# SCH_Boat_automator_2_0_2022-10-05.net
KiCad netlist of a schematic drawn in EasyEDA
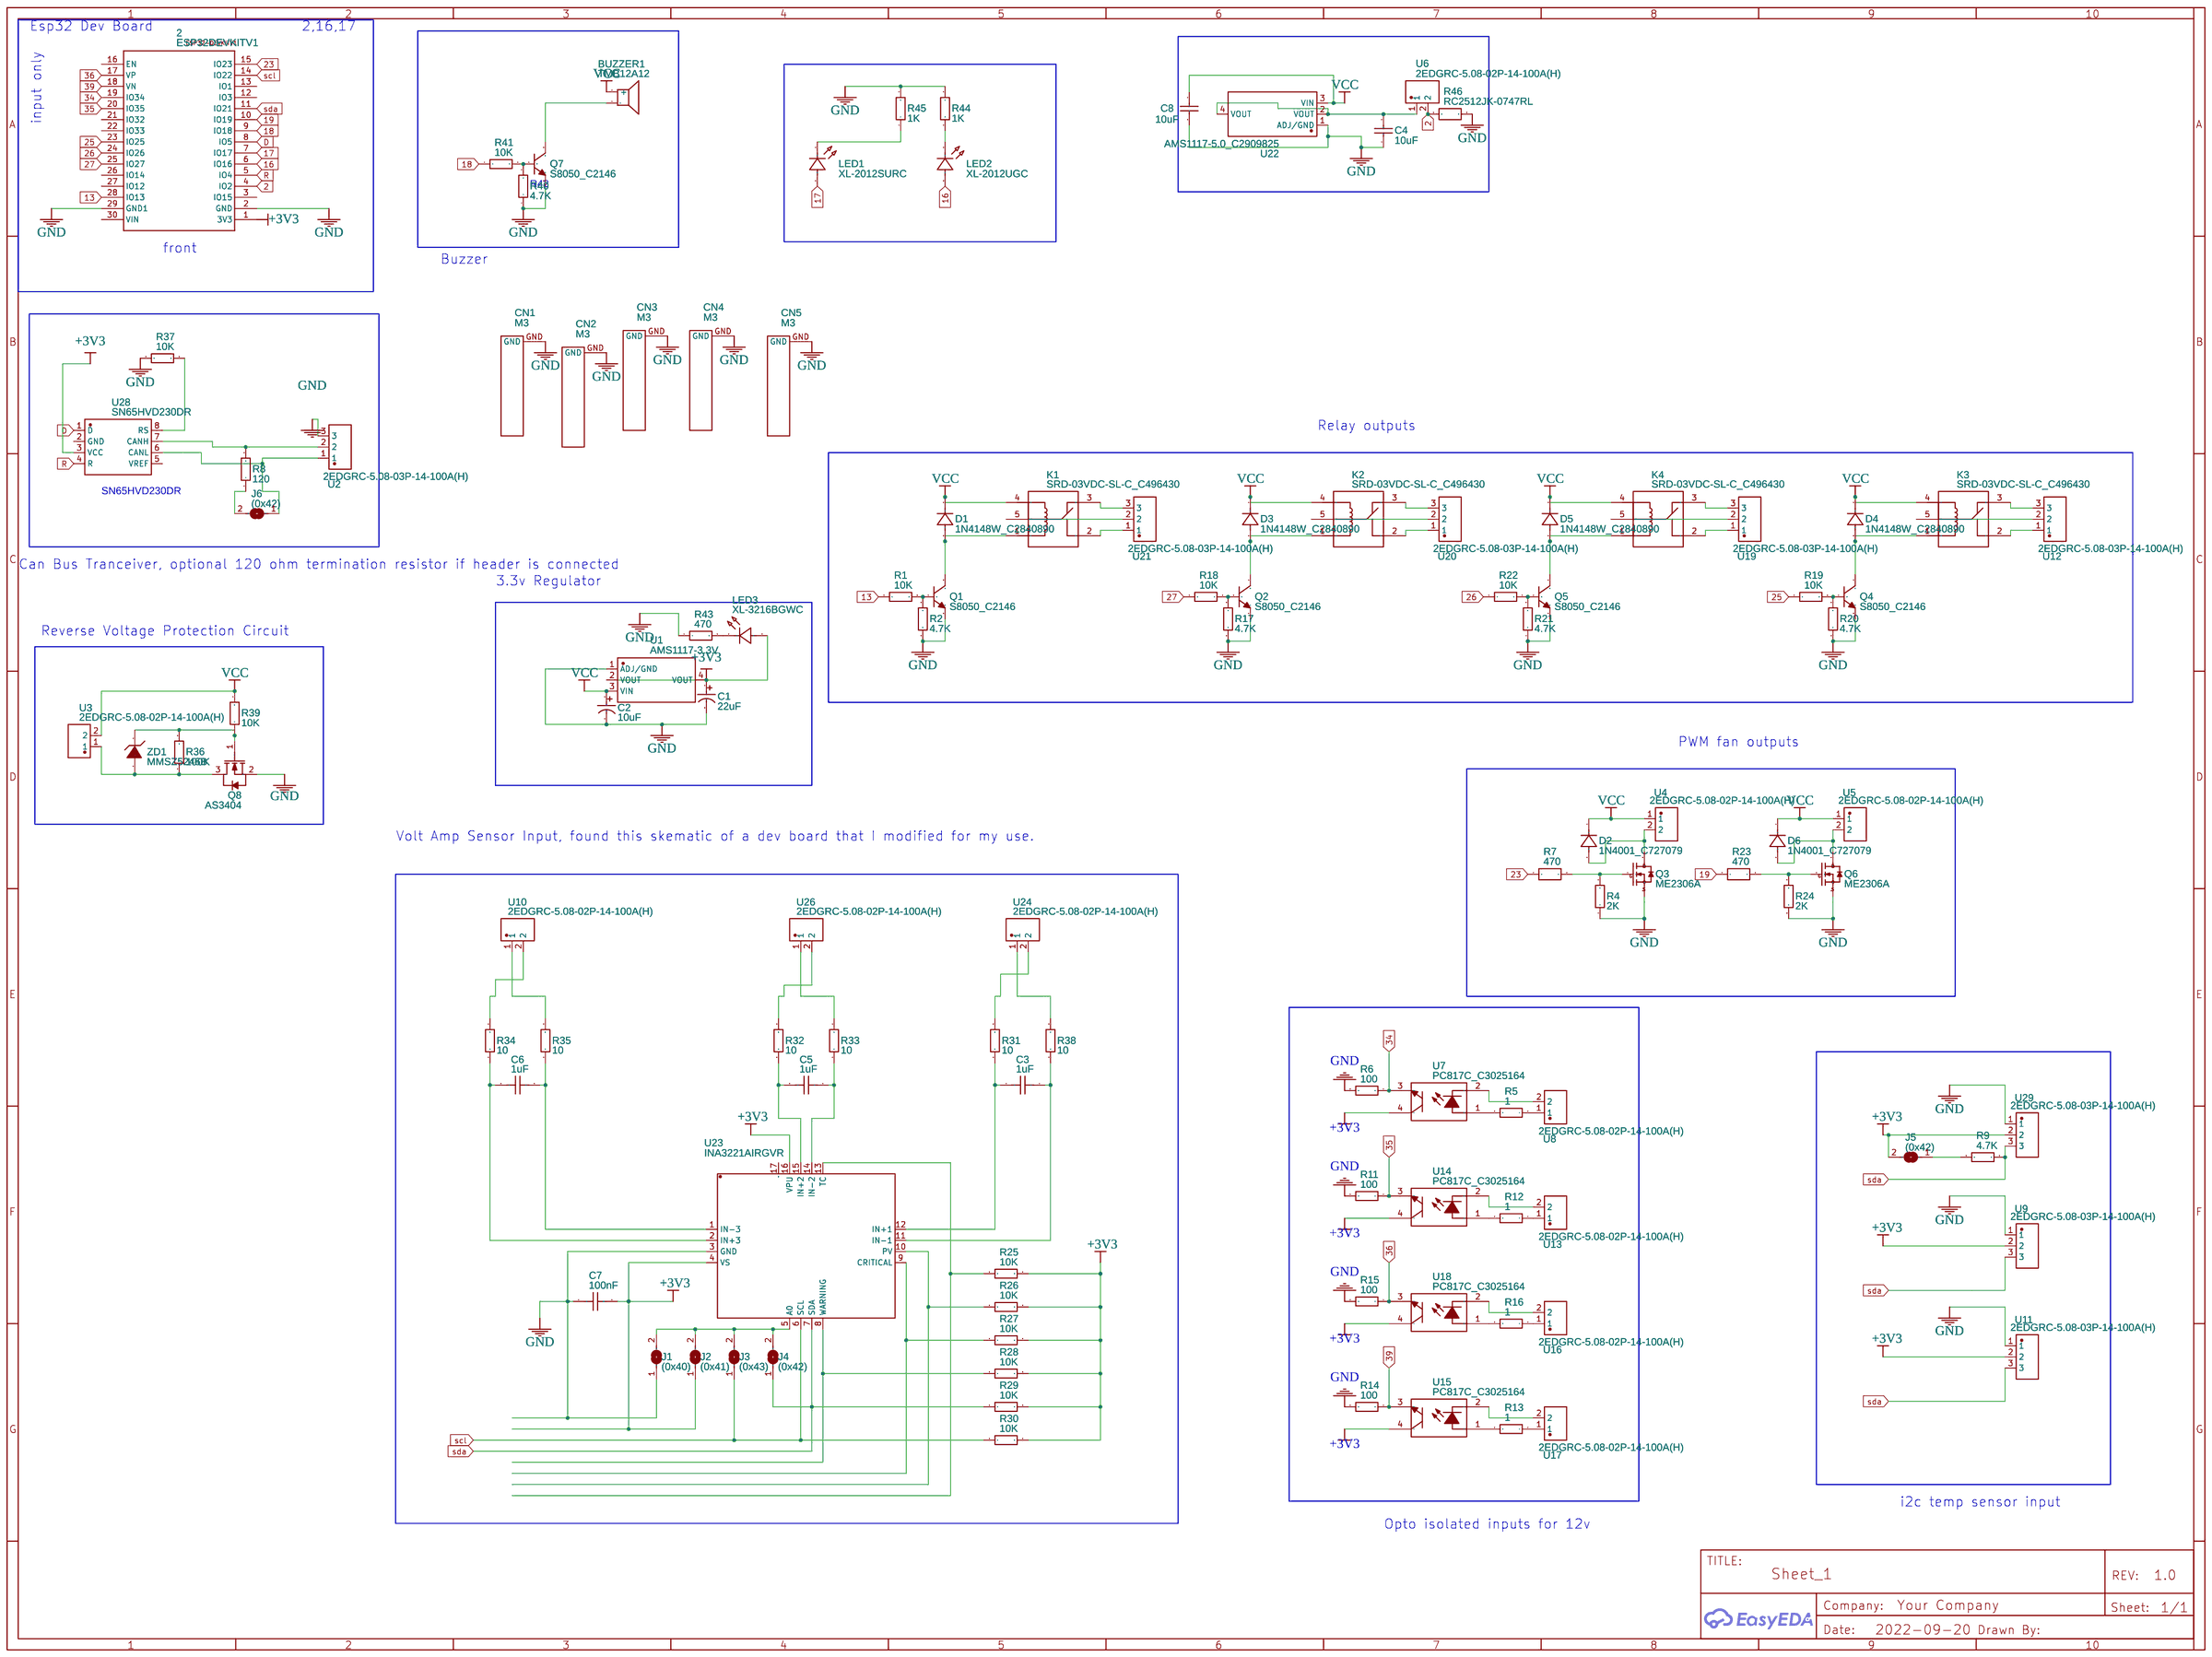
[diagram p0: schematic sheet]

(export (version "E")
  (design (tool "Eeschema 10.0.6"))
  (components
    (comp (ref "2") (value "ESP32DEVKITV1") (libsource (lib "") (part "ESP32DEVKITV1")))
    (comp (ref "BUZZER1")
      (value "TMB12A12")
      (fields (field (name "BOM_Supplier Part") "C96079"))
      (libsource (lib "") (part "TMB12A12"))
    )
    (comp (ref "C1")
      (value "22uF")
      (fields
        (field (name "BOM_Manufacturer Part") "RVT1C220M0405")
        (field (name "BOM_Supplier Part") "C72502")
      )
      (libsource (lib "") (part "RVT1C220M0405"))
    )
    (comp (ref "C2")
      (value "10uF")
      (fields
        (field (name "BOM_Manufacturer Part") "RVT1V100M0405")
        (field (name "BOM_Supplier Part") "C72485")
      )
      (libsource (lib "") (part "RVT1V100M0405-C72485"))
    )
    (comp (ref "C3")
      (value "1uF")
      (fields
        (field (name "BOM_Manufacturer Part") "CC0402KRX5R7BB105")
        (field (name "BOM_Supplier Part") "C325464")
      )
      (libsource (lib "") (part "CC0402KRX5R7BB105"))
    )
    (comp (ref "C4")
      (value "10uF")
      (fields
        (field (name "BOM_Manufacturer Part") "CC0805KKX5R8BB106")
        (field (name "BOM_Supplier Part") "C89831")
      )
      (libsource (lib "") (part "CC0805KKX5R8BB106"))
    )
    (comp (ref "C5")
      (value "1uF")
      (fields
        (field (name "BOM_Manufacturer Part") "CC0402KRX5R7BB105")
        (field (name "BOM_Supplier Part") "C325464")
      )
      (libsource (lib "") (part "CC0402KRX5R7BB105"))
    )
    (comp (ref "C6")
      (value "1uF")
      (fields
        (field (name "BOM_Manufacturer Part") "CC0402KRX5R7BB105")
        (field (name "BOM_Supplier Part") "C325464")
      )
      (libsource (lib "") (part "CC0402KRX5R7BB105"))
    )
    (comp (ref "C7")
      (value "100nF")
      (fields
        (field (name "BOM_Manufacturer Part") "CC0402KRX5R6BB104")
        (field (name "BOM_Supplier Part") "C129131")
      )
      (libsource (lib "") (part "CC0402KRX5R6BB104"))
    )
    (comp (ref "C8")
      (value "10uF")
      (fields
        (field (name "BOM_Manufacturer Part") "CC0805KKX5R8BB106")
        (field (name "BOM_Supplier Part") "C89831")
      )
      (libsource (lib "") (part "CC0805KKX5R8BB106"))
    )
    (comp (ref "CN1")
      (value "M3")
      (fields (field (name "BOM_Manufacturer Part") "XH-9A") (field (name "BOM_Supplier Part") "C8887"))
      (libsource (lib "") (part "M3"))
    )
    (comp (ref "CN2")
      (value "M3")
      (fields (field (name "BOM_Manufacturer Part") "XH-9A") (field (name "BOM_Supplier Part") "C8887"))
      (libsource (lib "") (part "M3"))
    )
    (comp (ref "CN3")
      (value "M3")
      (fields (field (name "BOM_Manufacturer Part") "XH-9A") (field (name "BOM_Supplier Part") "C8887"))
      (libsource (lib "") (part "M3"))
    )
    (comp (ref "CN4")
      (value "M3")
      (fields (field (name "BOM_Manufacturer Part") "XH-9A") (field (name "BOM_Supplier Part") "C8887"))
      (libsource (lib "") (part "M3"))
    )
    (comp (ref "CN5")
      (value "M3")
      (fields (field (name "BOM_Manufacturer Part") "XH-9A") (field (name "BOM_Supplier Part") "C8887"))
      (libsource (lib "") (part "M3"))
    )
    (comp (ref "D1")
      (value "1N4148W_C2840890")
      (fields (field (name "BOM_Manufacturer Part") "1N4148W") (field (name "BOM_Supplier Part") "C2840890"))
      (libsource (lib "") (part "1N4148W_C2840890"))
    )
    (comp (ref "D2")
      (value "1N4001_C727079")
      (fields (field (name "BOM_Manufacturer Part") "1N4001") (field (name "BOM_Supplier Part") "C727079"))
      (libsource (lib "") (part "1N4001_C727079"))
    )
    (comp (ref "D3")
      (value "1N4148W_C2840890")
      (fields (field (name "BOM_Manufacturer Part") "1N4148W") (field (name "BOM_Supplier Part") "C2840890"))
      (libsource (lib "") (part "1N4148W_C2840890"))
    )
    (comp (ref "D4")
      (value "1N4148W_C2840890")
      (fields (field (name "BOM_Manufacturer Part") "1N4148W") (field (name "BOM_Supplier Part") "C2840890"))
      (libsource (lib "") (part "1N4148W_C2840890"))
    )
    (comp (ref "D5")
      (value "1N4148W_C2840890")
      (fields (field (name "BOM_Manufacturer Part") "1N4148W") (field (name "BOM_Supplier Part") "C2840890"))
      (libsource (lib "") (part "1N4148W_C2840890"))
    )
    (comp (ref "D6")
      (value "1N4001_C727079")
      (fields (field (name "BOM_Manufacturer Part") "1N4001") (field (name "BOM_Supplier Part") "C727079"))
      (libsource (lib "") (part "1N4001_C727079"))
    )
    (comp (ref "J1")
      (value "(0x40)")
      (fields (field (name "BOM_Manufacturer Part") "?"))
      (libsource (lib "") (part "Unknown_585_400"))
    )
    (comp (ref "J2")
      (value "(0x41)")
      (fields (field (name "BOM_Manufacturer Part") "?"))
      (libsource (lib "") (part "Unknown_620_400"))
    )
    (comp (ref "J3")
      (value "(0x43)")
      (fields (field (name "BOM_Manufacturer Part") "?"))
      (libsource (lib "") (part "Unknown_655_400"))
    )
    (comp (ref "J4")
      (value "(0x42)")
      (fields (field (name "BOM_Manufacturer Part") "?"))
      (libsource (lib "") (part "Unknown_690_400"))
    )
    (comp (ref "J5")
      (value "(0x42)")
      (fields (field (name "BOM_Manufacturer Part") "?"))
      (libsource (lib "") (part "Unknown_1705_230"))
    )
    (comp (ref "J6")
      (value "(0x42)")
      (fields (field (name "BOM_Manufacturer Part") "?"))
      (libsource (lib "") (part "Unknown_215_-350"))
    )
    (comp (ref "K1")
      (value "SRD-03VDC-SL-C_C496430")
      (fields
        (field (name "BOM_Manufacturer Part") "SRD-03VDC-SL-C")
        (field (name "BOM_Supplier Part") "C496430")
      )
      (libsource (lib "") (part "SRD-03VDC-SL-C_C496430"))
    )
    (comp (ref "K2")
      (value "SRD-03VDC-SL-C_C496430")
      (fields
        (field (name "BOM_Manufacturer Part") "SRD-03VDC-SL-C")
        (field (name "BOM_Supplier Part") "C496430")
      )
      (libsource (lib "") (part "SRD-03VDC-SL-C_C496430"))
    )
    (comp (ref "K3")
      (value "SRD-03VDC-SL-C_C496430")
      (fields
        (field (name "BOM_Manufacturer Part") "SRD-03VDC-SL-C")
        (field (name "BOM_Supplier Part") "C496430")
      )
      (libsource (lib "") (part "SRD-03VDC-SL-C_C496430"))
    )
    (comp (ref "K4")
      (value "SRD-03VDC-SL-C_C496430")
      (fields
        (field (name "BOM_Manufacturer Part") "SRD-03VDC-SL-C")
        (field (name "BOM_Supplier Part") "C496430")
      )
      (libsource (lib "") (part "SRD-03VDC-SL-C_C496430"))
    )
    (comp (ref "LED1")
      (value "XL-2012SURC")
      (fields (field (name "BOM_Supplier Part") "C965812"))
      (libsource (lib "") (part "XL-2012SURC"))
    )
    (comp (ref "LED2")
      (value "XL-2012UGC")
      (fields (field (name "BOM_Supplier Part") "C965815"))
      (libsource (lib "") (part "XL-2012UGC"))
    )
    (comp (ref "LED3")
      (value "XL-3216BGWC")
      (fields (field (name "BOM_Supplier Part") "C965829"))
      (libsource (lib "") (part "XL-3216BGWC"))
    )
    (comp (ref "Q1")
      (value "S8050_C2146")
      (fields (field (name "BOM_Manufacturer Part") "S8050") (field (name "BOM_Supplier Part") "C2146"))
      (libsource (lib "") (part "S8050_C2146"))
    )
    (comp (ref "Q2")
      (value "S8050_C2146")
      (fields (field (name "BOM_Manufacturer Part") "S8050") (field (name "BOM_Supplier Part") "C2146"))
      (libsource (lib "") (part "S8050_C2146"))
    )
    (comp (ref "Q3")
      (value "ME2306A")
      (fields (field (name "BOM_Supplier Part") "C165219"))
      (libsource (lib "") (part "ME2306A"))
    )
    (comp (ref "Q4")
      (value "S8050_C2146")
      (fields (field (name "BOM_Manufacturer Part") "S8050") (field (name "BOM_Supplier Part") "C2146"))
      (libsource (lib "") (part "S8050_C2146"))
    )
    (comp (ref "Q5")
      (value "S8050_C2146")
      (fields (field (name "BOM_Manufacturer Part") "S8050") (field (name "BOM_Supplier Part") "C2146"))
      (libsource (lib "") (part "S8050_C2146"))
    )
    (comp (ref "Q6")
      (value "ME2306A")
      (fields (field (name "BOM_Supplier Part") "C165219"))
      (libsource (lib "") (part "ME2306A"))
    )
    (comp (ref "Q7")
      (value "S8050_C2146")
      (fields (field (name "BOM_Manufacturer Part") "S8050") (field (name "BOM_Supplier Part") "C2146"))
      (libsource (lib "") (part "S8050_C2146"))
    )
    (comp (ref "Q8")
      (value "AS3404")
      (fields (field (name "BOM_Supplier Part") "C232278"))
      (libsource (lib "") (part "AS3404"))
    )
    (comp (ref "R1")
      (value "10K")
      (fields
        (field (name "BOM_Manufacturer Part") "RC0603JR-0710KL")
        (field (name "BOM_Supplier Part") "C99198")
      )
      (libsource (lib "") (part "RC0603JR-0710KL"))
    )
    (comp (ref "R2")
      (value "4.7K")
      (fields
        (field (name "BOM_Manufacturer Part") "RC0603JR-074K7L")
        (field (name "BOM_Supplier Part") "C105428")
      )
      (libsource (lib "") (part "RC0603JR-074K7L"))
    )
    (comp (ref "R4")
      (value "2K")
      (fields
        (field (name "BOM_Manufacturer Part") "RC0603JR-072KL")
        (field (name "BOM_Supplier Part") "C105581")
      )
      (libsource (lib "") (part "RC0603JR-072KL"))
    )
    (comp (ref "R5")
      (value "1")
      (fields
        (field (name "BOM_Manufacturer Part") "RC0603FR-071RL")
        (field (name "BOM_Supplier Part") "C112305")
      )
      (libsource (lib "") (part "RC0603FR-071RL"))
    )
    (comp (ref "R6")
      (value "100")
      (fields
        (field (name "BOM_Manufacturer Part") "RC0603JR-07100RL")
        (field (name "BOM_Supplier Part") "C110091")
      )
      (libsource (lib "") (part "RC0603JR-07100RL"))
    )
    (comp (ref "R7")
      (value "470")
      (fields
        (field (name "BOM_Manufacturer Part") "AC0402FR-07470RL")
        (field (name "BOM_Supplier Part") "C227095")
      )
      (libsource (lib "") (part "AC0402FR-07470RL"))
    )
    (comp (ref "R8")
      (value "120")
      (fields
        (field (name "BOM_Manufacturer Part") "RC1206FR-07120RL")
        (field (name "BOM_Supplier Part") "C114928")
      )
      (libsource (lib "") (part "RC1206FR-07120RL"))
    )
    (comp (ref "R9")
      (value "4.7K")
      (fields
        (field (name "BOM_Manufacturer Part") "RC0603JR-074K7L")
        (field (name "BOM_Supplier Part") "C105428")
      )
      (libsource (lib "") (part "RC0603JR-074K7L_1"))
    )
    (comp (ref "R11")
      (value "100")
      (fields
        (field (name "BOM_Manufacturer Part") "RC0603JR-07100RL")
        (field (name "BOM_Supplier Part") "C110091")
      )
      (libsource (lib "") (part "RC0603JR-07100RL"))
    )
    (comp (ref "R12")
      (value "1")
      (fields
        (field (name "BOM_Manufacturer Part") "RC0603FR-071RL")
        (field (name "BOM_Supplier Part") "C112305")
      )
      (libsource (lib "") (part "RC0603FR-071RL"))
    )
    (comp (ref "R13")
      (value "1")
      (fields
        (field (name "BOM_Manufacturer Part") "RC0603FR-071RL")
        (field (name "BOM_Supplier Part") "C112305")
      )
      (libsource (lib "") (part "RC0603FR-071RL"))
    )
    (comp (ref "R14")
      (value "100")
      (fields
        (field (name "BOM_Manufacturer Part") "RC0603JR-07100RL")
        (field (name "BOM_Supplier Part") "C110091")
      )
      (libsource (lib "") (part "RC0603JR-07100RL"))
    )
    (comp (ref "R15")
      (value "100")
      (fields
        (field (name "BOM_Manufacturer Part") "RC0603JR-07100RL")
        (field (name "BOM_Supplier Part") "C110091")
      )
      (libsource (lib "") (part "RC0603JR-07100RL"))
    )
    (comp (ref "R16")
      (value "1")
      (fields
        (field (name "BOM_Manufacturer Part") "RC0603FR-071RL")
        (field (name "BOM_Supplier Part") "C112305")
      )
      (libsource (lib "") (part "RC0603FR-071RL"))
    )
    (comp (ref "R17")
      (value "4.7K")
      (fields
        (field (name "BOM_Manufacturer Part") "RC0603JR-074K7L")
        (field (name "BOM_Supplier Part") "C105428")
      )
      (libsource (lib "") (part "RC0603JR-074K7L"))
    )
    (comp (ref "R18")
      (value "10K")
      (fields
        (field (name "BOM_Manufacturer Part") "RC0603JR-0710KL")
        (field (name "BOM_Supplier Part") "C99198")
      )
      (libsource (lib "") (part "RC0603JR-0710KL"))
    )
    (comp (ref "R19")
      (value "10K")
      (fields
        (field (name "BOM_Manufacturer Part") "RC0603JR-0710KL")
        (field (name "BOM_Supplier Part") "C99198")
      )
      (libsource (lib "") (part "RC0603JR-0710KL"))
    )
    (comp (ref "R20")
      (value "4.7K")
      (fields
        (field (name "BOM_Manufacturer Part") "RC0603JR-074K7L")
        (field (name "BOM_Supplier Part") "C105428")
      )
      (libsource (lib "") (part "RC0603JR-074K7L"))
    )
    (comp (ref "R21")
      (value "4.7K")
      (fields
        (field (name "BOM_Manufacturer Part") "RC0603JR-074K7L")
        (field (name "BOM_Supplier Part") "C105428")
      )
      (libsource (lib "") (part "RC0603JR-074K7L"))
    )
    (comp (ref "R22")
      (value "10K")
      (fields
        (field (name "BOM_Manufacturer Part") "RC0603JR-0710KL")
        (field (name "BOM_Supplier Part") "C99198")
      )
      (libsource (lib "") (part "RC0603JR-0710KL"))
    )
    (comp (ref "R23")
      (value "470")
      (fields
        (field (name "BOM_Manufacturer Part") "AC0402FR-07470RL")
        (field (name "BOM_Supplier Part") "C227095")
      )
      (libsource (lib "") (part "AC0402FR-07470RL"))
    )
    (comp (ref "R24")
      (value "2K")
      (fields
        (field (name "BOM_Manufacturer Part") "RC0603JR-072KL")
        (field (name "BOM_Supplier Part") "C105581")
      )
      (libsource (lib "") (part "RC0603JR-072KL"))
    )
    (comp (ref "R25")
      (value "10K")
      (fields
        (field (name "BOM_Manufacturer Part") "RC0603JR-0710KL")
        (field (name "BOM_Supplier Part") "C99198")
      )
      (libsource (lib "") (part "RC0603JR-0710KL"))
    )
    (comp (ref "R26")
      (value "10K")
      (fields
        (field (name "BOM_Manufacturer Part") "RC0603JR-0710KL")
        (field (name "BOM_Supplier Part") "C99198")
      )
      (libsource (lib "") (part "RC0603JR-0710KL"))
    )
    (comp (ref "R27")
      (value "10K")
      (fields
        (field (name "BOM_Manufacturer Part") "RC0603JR-0710KL")
        (field (name "BOM_Supplier Part") "C99198")
      )
      (libsource (lib "") (part "RC0603JR-0710KL"))
    )
    (comp (ref "R28")
      (value "10K")
      (fields
        (field (name "BOM_Manufacturer Part") "RC0603JR-0710KL")
        (field (name "BOM_Supplier Part") "C99198")
      )
      (libsource (lib "") (part "RC0603JR-0710KL"))
    )
    (comp (ref "R29")
      (value "10K")
      (fields
        (field (name "BOM_Manufacturer Part") "RC0603JR-0710KL")
        (field (name "BOM_Supplier Part") "C99198")
      )
      (libsource (lib "") (part "RC0603JR-0710KL"))
    )
    (comp (ref "R30")
      (value "10K")
      (fields
        (field (name "BOM_Manufacturer Part") "RC0603JR-0710KL")
        (field (name "BOM_Supplier Part") "C99198")
      )
      (libsource (lib "") (part "RC0603JR-0710KL"))
    )
    (comp (ref "R31")
      (value "10")
      (fields
        (field (name "BOM_Manufacturer Part") "RC0603FR-0710RL")
        (field (name "BOM_Supplier Part") "C109318")
      )
      (libsource (lib "") (part "RC0603FR-0710RL"))
    )
    (comp (ref "R32")
      (value "10")
      (fields
        (field (name "BOM_Manufacturer Part") "RC0603FR-0710RL")
        (field (name "BOM_Supplier Part") "C109318")
      )
      (libsource (lib "") (part "RC0603FR-0710RL"))
    )
    (comp (ref "R33")
      (value "10")
      (fields
        (field (name "BOM_Manufacturer Part") "RC0603FR-0710RL")
        (field (name "BOM_Supplier Part") "C109318")
      )
      (libsource (lib "") (part "RC0603FR-0710RL"))
    )
    (comp (ref "R34")
      (value "10")
      (fields
        (field (name "BOM_Manufacturer Part") "RC0603FR-0710RL")
        (field (name "BOM_Supplier Part") "C109318")
      )
      (libsource (lib "") (part "RC0603FR-0710RL"))
    )
    (comp (ref "R35")
      (value "10")
      (fields
        (field (name "BOM_Manufacturer Part") "RC0603FR-0710RL")
        (field (name "BOM_Supplier Part") "C109318")
      )
      (libsource (lib "") (part "RC0603FR-0710RL"))
    )
    (comp (ref "R36")
      (value "100K")
      (fields
        (field (name "BOM_Manufacturer Part") "RC0603FR-07100KL")
        (field (name "BOM_Supplier Part") "C14675")
      )
      (libsource (lib "") (part "RC0603FR-07100KL"))
    )
    (comp (ref "R37")
      (value "10K")
      (fields
        (field (name "BOM_Manufacturer Part") "RC0603JR-0710KL")
        (field (name "BOM_Supplier Part") "C99198")
      )
      (libsource (lib "") (part "RC0603JR-0710KL"))
    )
    (comp (ref "R38")
      (value "10")
      (fields
        (field (name "BOM_Manufacturer Part") "RC0603FR-0710RL")
        (field (name "BOM_Supplier Part") "C109318")
      )
      (libsource (lib "") (part "RC0603FR-0710RL"))
    )
    (comp (ref "R39")
      (value "10K")
      (fields
        (field (name "BOM_Manufacturer Part") "RC0603JR-0710KL")
        (field (name "BOM_Supplier Part") "C99198")
      )
      (libsource (lib "") (part "RC0603JR-0710KL_1"))
    )
    (comp (ref "R40")
      (value "4.7K")
      (fields
        (field (name "BOM_Manufacturer Part") "RC0603JR-074K7L")
        (field (name "BOM_Supplier Part") "C105428")
      )
      (libsource (lib "") (part "RC0603JR-074K7L"))
    )
    (comp (ref "R41")
      (value "10K")
      (fields
        (field (name "BOM_Manufacturer Part") "RC0603JR-0710KL")
        (field (name "BOM_Supplier Part") "C99198")
      )
      (libsource (lib "") (part "RC0603JR-0710KL"))
    )
    (comp (ref "R43")
      (value "470")
      (fields
        (field (name "BOM_Manufacturer Part") "RC1206JR-07470RL")
        (field (name "BOM_Supplier Part") "C114948")
      )
      (libsource (lib "") (part "RC1206JR-07470RL"))
    )
    (comp (ref "R44")
      (value "1K")
      (fields
        (field (name "BOM_Manufacturer Part") "RC1206JR-071KL")
        (field (name "BOM_Supplier Part") "C112223")
      )
      (libsource (lib "") (part "RC1206JR-071KL"))
    )
    (comp (ref "R45")
      (value "1K")
      (fields
        (field (name "BOM_Manufacturer Part") "RC1206JR-071KL")
        (field (name "BOM_Supplier Part") "C112223")
      )
      (libsource (lib "") (part "RC1206JR-071KL"))
    )
    (comp (ref "R46")
      (value "RC2512JK-0747RL")
      (fields (field (name "BOM_Supplier Part") "C513678"))
      (libsource (lib "") (part "RC2512JK-0747RL"))
    )
    (comp (ref "U1")
      (value "AMS1117-3.3V")
      (fields (field (name "BOM_Supplier Part") "C2688239"))
      (libsource (lib "") (part "AMS1117-3.3V"))
    )
    (comp (ref "U2")
      (value "2EDGRC-5.08-03P-14-100A(H)")
      (fields (field (name "BOM_Supplier Part") "C669315"))
      (libsource (lib "") (part "2EDGRC-5.08-03P-14-100A(H)"))
    )
    (comp (ref "U3")
      (value "2EDGRC-5.08-02P-14-100A(H)")
      (fields (field (name "BOM_Supplier Part") "C669314"))
      (libsource (lib "") (part "2EDGRC-5.08-02P-14-100A(H)_3"))
    )
    (comp (ref "U4")
      (value "2EDGRC-5.08-02P-14-100A(H)")
      (fields (field (name "BOM_Supplier Part") "C669314"))
      (libsource (lib "") (part "2EDGRC-5.08-02P-14-100A(H)_2"))
    )
    (comp (ref "U5")
      (value "2EDGRC-5.08-02P-14-100A(H)")
      (fields (field (name "BOM_Supplier Part") "C669314"))
      (libsource (lib "") (part "2EDGRC-5.08-02P-14-100A(H)_2"))
    )
    (comp (ref "U6")
      (value "2EDGRC-5.08-02P-14-100A(H)")
      (fields (field (name "BOM_Supplier Part") "C669314"))
      (libsource (lib "") (part "2EDGRC-5.08-02P-14-100A(H)"))
    )
    (comp (ref "U7")
      (value "PC817C_C3025164")
      (fields (field (name "BOM_Manufacturer Part") "PC817C") (field (name "BOM_Supplier Part") "C3025164"))
      (libsource (lib "") (part "PC817C_C3025164"))
    )
    (comp (ref "U8")
      (value "2EDGRC-5.08-02P-14-100A(H)")
      (fields (field (name "BOM_Supplier Part") "C669314"))
      (libsource (lib "") (part "2EDGRC-5.08-02P-14-100A(H)_1"))
    )
    (comp (ref "U9")
      (value "2EDGRC-5.08-03P-14-100A(H)")
      (fields (field (name "BOM_Supplier Part") "C669315"))
      (libsource (lib "") (part "2EDGRC-5.08-03P-14-100A(H)_1"))
    )
    (comp (ref "U10")
      (value "2EDGRC-5.08-02P-14-100A(H)")
      (fields (field (name "BOM_Supplier Part") "C669314"))
      (libsource (lib "") (part "2EDGRC-5.08-02P-14-100A(H)"))
    )
    (comp (ref "U11")
      (value "2EDGRC-5.08-03P-14-100A(H)")
      (fields (field (name "BOM_Supplier Part") "C669315"))
      (libsource (lib "") (part "2EDGRC-5.08-03P-14-100A(H)_1"))
    )
    (comp (ref "U12")
      (value "2EDGRC-5.08-03P-14-100A(H)")
      (fields (field (name "BOM_Supplier Part") "C669315"))
      (libsource (lib "") (part "2EDGRC-5.08-03P-14-100A(H)"))
    )
    (comp (ref "U13")
      (value "2EDGRC-5.08-02P-14-100A(H)")
      (fields (field (name "BOM_Supplier Part") "C669314"))
      (libsource (lib "") (part "2EDGRC-5.08-02P-14-100A(H)_1"))
    )
    (comp (ref "U14")
      (value "PC817C_C3025164")
      (fields (field (name "BOM_Manufacturer Part") "PC817C") (field (name "BOM_Supplier Part") "C3025164"))
      (libsource (lib "") (part "PC817C_C3025164"))
    )
    (comp (ref "U15")
      (value "PC817C_C3025164")
      (fields (field (name "BOM_Manufacturer Part") "PC817C") (field (name "BOM_Supplier Part") "C3025164"))
      (libsource (lib "") (part "PC817C_C3025164"))
    )
    (comp (ref "U16")
      (value "2EDGRC-5.08-02P-14-100A(H)")
      (fields (field (name "BOM_Supplier Part") "C669314"))
      (libsource (lib "") (part "2EDGRC-5.08-02P-14-100A(H)_1"))
    )
    (comp (ref "U17")
      (value "2EDGRC-5.08-02P-14-100A(H)")
      (fields (field (name "BOM_Supplier Part") "C669314"))
      (libsource (lib "") (part "2EDGRC-5.08-02P-14-100A(H)_1"))
    )
    (comp (ref "U18")
      (value "PC817C_C3025164")
      (fields (field (name "BOM_Manufacturer Part") "PC817C") (field (name "BOM_Supplier Part") "C3025164"))
      (libsource (lib "") (part "PC817C_C3025164"))
    )
    (comp (ref "U19")
      (value "2EDGRC-5.08-03P-14-100A(H)")
      (fields (field (name "BOM_Supplier Part") "C669315"))
      (libsource (lib "") (part "2EDGRC-5.08-03P-14-100A(H)"))
    )
    (comp (ref "U20")
      (value "2EDGRC-5.08-03P-14-100A(H)")
      (fields (field (name "BOM_Supplier Part") "C669315"))
      (libsource (lib "") (part "2EDGRC-5.08-03P-14-100A(H)"))
    )
    (comp (ref "U21")
      (value "2EDGRC-5.08-03P-14-100A(H)")
      (fields (field (name "BOM_Supplier Part") "C669315"))
      (libsource (lib "") (part "2EDGRC-5.08-03P-14-100A(H)"))
    )
    (comp (ref "U22")
      (value "AMS1117-5.0_C2909825")
      (fields
        (field (name "BOM_Manufacturer Part") "AMS1117-5.0")
        (field (name "BOM_Supplier Part") "C2909825")
      )
      (libsource (lib "") (part "AMS1117-5.0_C2909825"))
    )
    (comp (ref "U23")
      (value "INA3221AIRGVR")
      (fields (field (name "BOM_Supplier Part") "C181255"))
      (libsource (lib "") (part "INA3221AIRGVR"))
    )
    (comp (ref "U24")
      (value "2EDGRC-5.08-02P-14-100A(H)")
      (fields (field (name "BOM_Supplier Part") "C669314"))
      (libsource (lib "") (part "2EDGRC-5.08-02P-14-100A(H)"))
    )
    (comp (ref "U26")
      (value "2EDGRC-5.08-02P-14-100A(H)")
      (fields (field (name "BOM_Supplier Part") "C669314"))
      (libsource (lib "") (part "2EDGRC-5.08-02P-14-100A(H)"))
    )
    (comp (ref "U28")
      (value "SN65HVD230DR")
      (fields (field (name "BOM_Supplier Part") "C12084"))
      (libsource (lib "") (part "SN65HVD230DR"))
    )
    (comp (ref "U29")
      (value "2EDGRC-5.08-03P-14-100A(H)")
      (fields (field (name "BOM_Supplier Part") "C669315"))
      (libsource (lib "") (part "2EDGRC-5.08-03P-14-100A(H)_1"))
    )
    (comp (ref "ZD1")
      (value "MMSZ5246B")
      (fields (field (name "BOM_Supplier Part") "C21544"))
      (libsource (lib "") (part "MMSZ5246B"))
    )
  )
  (nets
    (net (code "1") (name "+3V3") (class "Default")
      (node (ref "2") (pin "1") (pinfunction "3V3_1") (pintype "bidirectional"))
      (node (ref "C1") (pin "1") (pinfunction "1_1") (pintype "input"))
      (node (ref "C7") (pin "2") (pinfunction "2_2") (pintype "unspecified"))
      (node (ref "J2") (pin "1") (pinfunction "1_1") (pintype "bidirectional"))
      (node (ref "J5") (pin "2") (pinfunction "2_2") (pintype "bidirectional"))
      (node (ref "LED3") (pin "2") (pinfunction "A_2") (pintype "unspecified"))
      (node (ref "R25") (pin "2") (pinfunction "2_2") (pintype "input"))
      (node (ref "R26") (pin "2") (pinfunction "2_2") (pintype "input"))
      (node (ref "R27") (pin "2") (pinfunction "2_2") (pintype "input"))
      (node (ref "R28") (pin "2") (pinfunction "2_2") (pintype "input"))
      (node (ref "R29") (pin "2") (pinfunction "2_2") (pintype "input"))
      (node (ref "R30") (pin "2") (pinfunction "2_2") (pintype "input"))
      (node (ref "U1") (pin "2") (pinfunction "VOUT_2") (pintype "unspecified"))
      (node (ref "U1") (pin "4") (pinfunction "VOUT_4") (pintype "unspecified"))
      (node (ref "U11") (pin "2") (pinfunction "2_2") (pintype "unspecified"))
      (node (ref "U14") (pin "4") (pinfunction "4_4") (pintype "unspecified"))
      (node (ref "U15") (pin "4") (pinfunction "4_4") (pintype "unspecified"))
      (node (ref "U18") (pin "4") (pinfunction "4_4") (pintype "unspecified"))
      (node (ref "U23") (pin "16") (pinfunction "VPU_16") (pintype "unspecified"))
      (node (ref "U23") (pin "4") (pinfunction "VS_4") (pintype "unspecified"))
      (node (ref "U28") (pin "3") (pinfunction "VCC_3") (pintype "unspecified"))
      (node (ref "U29") (pin "2") (pinfunction "2_2") (pintype "unspecified"))
      (node (ref "U7") (pin "4") (pinfunction "4_4") (pintype "unspecified"))
      (node (ref "U9") (pin "2") (pinfunction "2_2") (pintype "unspecified"))
    )
    (net (code "2") (name "2") (class "Default")
      (node (ref "2") (pin "4") (pinfunction "IO2_4") (pintype "bidirectional"))
      (node (ref "R46") (pin "1") (pinfunction "1_1") (pintype "unspecified"))
      (node (ref "U6") (pin "2") (pinfunction "2_2") (pintype "unspecified"))
    )
    (net (code "3") (name "13") (class "Default")
      (node (ref "2") (pin "28") (pinfunction "IO13_28") (pintype "bidirectional"))
      (node (ref "R1") (pin "1") (pinfunction "1_1") (pintype "input"))
    )
    (net (code "4") (name "16") (class "Default")
      (node (ref "2") (pin "6") (pinfunction "IO16_6") (pintype "bidirectional"))
      (node (ref "LED2") (pin "2") (pinfunction "A_2") (pintype "unspecified"))
    )
    (net (code "5") (name "17") (class "Default")
      (node (ref "2") (pin "7") (pinfunction "IO17_7") (pintype "bidirectional"))
      (node (ref "LED1") (pin "2") (pinfunction "A_2") (pintype "unspecified"))
    )
    (net (code "6") (name "18") (class "Default")
      (node (ref "2") (pin "9") (pinfunction "IO18_9") (pintype "bidirectional"))
      (node (ref "R41") (pin "1") (pinfunction "1_1") (pintype "input"))
    )
    (net (code "7") (name "19") (class "Default")
      (node (ref "2") (pin "10") (pinfunction "IO19_10") (pintype "bidirectional"))
      (node (ref "R23") (pin "1") (pinfunction "1_1") (pintype "unspecified"))
    )
    (net (code "8") (name "23") (class "Default")
      (node (ref "2") (pin "15") (pinfunction "IO23_15") (pintype "bidirectional"))
      (node (ref "R7") (pin "1") (pinfunction "1_1") (pintype "unspecified"))
    )
    (net (code "9") (name "25") (class "Default")
      (node (ref "2") (pin "23") (pinfunction "IO25_23") (pintype "bidirectional"))
      (node (ref "R19") (pin "1") (pinfunction "1_1") (pintype "input"))
    )
    (net (code "10") (name "26") (class "Default")
      (node (ref "2") (pin "24") (pinfunction "IO26_24") (pintype "bidirectional"))
      (node (ref "R22") (pin "1") (pinfunction "1_1") (pintype "input"))
    )
    (net (code "11") (name "27") (class "Default")
      (node (ref "2") (pin "25") (pinfunction "IO27_25") (pintype "bidirectional"))
      (node (ref "R18") (pin "1") (pinfunction "1_1") (pintype "input"))
    )
    (net (code "12") (name "34") (class "Default")
      (node (ref "2") (pin "19") (pinfunction "IO34_19") (pintype "bidirectional"))
      (node (ref "R6") (pin "1") (pinfunction "1_1") (pintype "input"))
      (node (ref "U7") (pin "3") (pinfunction "3_3") (pintype "unspecified"))
    )
    (net (code "13") (name "35") (class "Default")
      (node (ref "2") (pin "20") (pinfunction "IO35_20") (pintype "bidirectional"))
      (node (ref "R11") (pin "1") (pinfunction "1_1") (pintype "input"))
      (node (ref "U14") (pin "3") (pinfunction "3_3") (pintype "unspecified"))
    )
    (net (code "14") (name "36") (class "Default")
      (node (ref "2") (pin "17") (pinfunction "VP_17") (pintype "bidirectional"))
      (node (ref "R15") (pin "1") (pinfunction "1_1") (pintype "input"))
      (node (ref "U18") (pin "3") (pinfunction "3_3") (pintype "unspecified"))
    )
    (net (code "15") (name "39") (class "Default")
      (node (ref "2") (pin "18") (pinfunction "VN_18") (pintype "bidirectional"))
      (node (ref "R14") (pin "1") (pinfunction "1_1") (pintype "input"))
      (node (ref "U15") (pin "3") (pinfunction "3_3") (pintype "unspecified"))
    )
    (net (code "16") (name "D") (class "Default")
      (node (ref "2") (pin "8") (pinfunction "IO5_8") (pintype "bidirectional"))
      (node (ref "U28") (pin "1") (pinfunction "D_1") (pintype "unspecified"))
    )
    (net (code "17") (name "GND") (class "Default")
      (node (ref "2") (pin "2") (pinfunction "GND_2") (pintype "bidirectional"))
      (node (ref "2") (pin "29") (pinfunction "GND1_29") (pintype "bidirectional"))
      (node (ref "C1") (pin "2") (pinfunction "2_2") (pintype "input"))
      (node (ref "C2") (pin "2") (pinfunction "2_2") (pintype "input"))
      (node (ref "C4") (pin "1") (pinfunction "1_1") (pintype "input"))
      (node (ref "C7") (pin "1") (pinfunction "1_1") (pintype "unspecified"))
      (node (ref "C8") (pin "1") (pinfunction "1_1") (pintype "input"))
      (node (ref "CN1") (pin "GND") (pinfunction "GND_GND") (pintype "unspecified"))
      (node (ref "CN2") (pin "GND") (pinfunction "GND_GND") (pintype "unspecified"))
      (node (ref "CN3") (pin "GND") (pinfunction "GND_GND") (pintype "unspecified"))
      (node (ref "CN4") (pin "GND") (pinfunction "GND_GND") (pintype "unspecified"))
      (node (ref "CN5") (pin "GND") (pinfunction "GND_GND") (pintype "unspecified"))
      (node (ref "J1") (pin "1") (pinfunction "1_1") (pintype "bidirectional"))
      (node (ref "Q1") (pin "2") (pinfunction "E_2") (pintype "unspecified"))
      (node (ref "Q2") (pin "2") (pinfunction "E_2") (pintype "unspecified"))
      (node (ref "Q3") (pin "2") (pinfunction "S_2") (pintype "unspecified"))
      (node (ref "Q4") (pin "2") (pinfunction "E_2") (pintype "unspecified"))
      (node (ref "Q5") (pin "2") (pinfunction "E_2") (pintype "unspecified"))
      (node (ref "Q6") (pin "2") (pinfunction "S_2") (pintype "unspecified"))
      (node (ref "Q7") (pin "2") (pinfunction "E_2") (pintype "unspecified"))
      (node (ref "Q8") (pin "2") (pinfunction "S_2") (pintype "unspecified"))
      (node (ref "R11") (pin "2") (pinfunction "2_2") (pintype "input"))
      (node (ref "R14") (pin "2") (pinfunction "2_2") (pintype "input"))
      (node (ref "R15") (pin "2") (pinfunction "2_2") (pintype "input"))
      (node (ref "R17") (pin "1") (pinfunction "1_1") (pintype "input"))
      (node (ref "R2") (pin "1") (pinfunction "1_1") (pintype "input"))
      (node (ref "R20") (pin "1") (pinfunction "1_1") (pintype "input"))
      (node (ref "R21") (pin "1") (pinfunction "1_1") (pintype "input"))
      (node (ref "R24") (pin "1") (pinfunction "1_1") (pintype "input"))
      (node (ref "R37") (pin "1") (pinfunction "1_1") (pintype "input"))
      (node (ref "R4") (pin "1") (pinfunction "1_1") (pintype "input"))
      (node (ref "R40") (pin "1") (pinfunction "1_1") (pintype "input"))
      (node (ref "R43") (pin "1") (pinfunction "1_1") (pintype "input"))
      (node (ref "R44") (pin "2") (pinfunction "2_2") (pintype "input"))
      (node (ref "R45") (pin "2") (pinfunction "2_2") (pintype "input"))
      (node (ref "R46") (pin "2") (pinfunction "2_2") (pintype "unspecified"))
      (node (ref "R6") (pin "2") (pinfunction "2_2") (pintype "input"))
      (node (ref "U1") (pin "1") (pinfunction "ADJ/GND_1") (pintype "unspecified"))
      (node (ref "U11") (pin "1") (pinfunction "1_1") (pintype "unspecified"))
      (node (ref "U2") (pin "3") (pinfunction "3_3") (pintype "unspecified"))
      (node (ref "U22") (pin "1") (pinfunction "ADJ/GND_1") (pintype "unspecified"))
      (node (ref "U23") (pin "3") (pinfunction "GND_3") (pintype "unspecified"))
      (node (ref "U29") (pin "1") (pinfunction "1_1") (pintype "unspecified"))
      (node (ref "U9") (pin "1") (pinfunction "1_1") (pintype "unspecified"))
    )
    (net (code "18") (name "Net-(C4-Pad2)") (class "Default")
      (node (ref "C4") (pin "2") (pinfunction "2_2") (pintype "input"))
      (node (ref "U22") (pin "2") (pinfunction "VOUT_2") (pintype "unspecified"))
      (node (ref "U22") (pin "4") (pinfunction "VOUT_4") (pintype "unspecified"))
      (node (ref "U6") (pin "1") (pinfunction "1_1") (pintype "unspecified"))
    )
    (net (code "19") (name "Net-(D1-A)") (class "Default")
      (node (ref "D1") (pin "2") (pinfunction "A_2") (pintype "unspecified"))
      (node (ref "K1") (pin "1") (pinfunction "1_1") (pintype "unspecified"))
      (node (ref "Q1") (pin "3") (pinfunction "C_3") (pintype "unspecified"))
    )
    (net (code "20") (name "Net-(D2-A)") (class "Default")
      (node (ref "D2") (pin "2") (pinfunction "A_2") (pintype "unspecified"))
      (node (ref "Q3") (pin "3") (pinfunction "D_3") (pintype "unspecified"))
      (node (ref "U4") (pin "2") (pinfunction "2_2") (pintype "unspecified"))
    )
    (net (code "21") (name "Net-(D3-A)") (class "Default")
      (node (ref "D3") (pin "2") (pinfunction "A_2") (pintype "unspecified"))
      (node (ref "K2") (pin "1") (pinfunction "1_1") (pintype "unspecified"))
      (node (ref "Q2") (pin "3") (pinfunction "C_3") (pintype "unspecified"))
    )
    (net (code "22") (name "Net-(D4-A)") (class "Default")
      (node (ref "D4") (pin "2") (pinfunction "A_2") (pintype "unspecified"))
      (node (ref "K3") (pin "1") (pinfunction "1_1") (pintype "unspecified"))
      (node (ref "Q4") (pin "3") (pinfunction "C_3") (pintype "unspecified"))
    )
    (net (code "23") (name "Net-(D5-A)") (class "Default")
      (node (ref "D5") (pin "2") (pinfunction "A_2") (pintype "unspecified"))
      (node (ref "K4") (pin "1") (pinfunction "1_1") (pintype "unspecified"))
      (node (ref "Q5") (pin "3") (pinfunction "C_3") (pintype "unspecified"))
    )
    (net (code "24") (name "Net-(D6-A)") (class "Default")
      (node (ref "D6") (pin "2") (pinfunction "A_2") (pintype "unspecified"))
      (node (ref "Q6") (pin "3") (pinfunction "D_3") (pintype "unspecified"))
      (node (ref "U5") (pin "2") (pinfunction "2_2") (pintype "unspecified"))
    )
    (net (code "25") (name "Net-(J5-Pad1)") (class "Default")
      (node (ref "J5") (pin "1") (pinfunction "1_1") (pintype "bidirectional"))
      (node (ref "R9") (pin "2") (pinfunction "2_2") (pintype "input"))
    )
    (net (code "26") (name "Net-(J6-Pad2)") (class "Default")
      (node (ref "J6") (pin "2") (pinfunction "2_2") (pintype "bidirectional"))
      (node (ref "R8") (pin "1") (pinfunction "1_1") (pintype "input"))
    )
    (net (code "27") (name "Net-(K1-Pad2)") (class "Default")
      (node (ref "K1") (pin "2") (pinfunction "2_2") (pintype "unspecified"))
      (node (ref "U21") (pin "1") (pinfunction "1_1") (pintype "unspecified"))
    )
    (net (code "28") (name "Net-(K1-Pad3)") (class "Default")
      (node (ref "K1") (pin "3") (pinfunction "3_3") (pintype "unspecified"))
      (node (ref "U21") (pin "3") (pinfunction "3_3") (pintype "unspecified"))
    )
    (net (code "29") (name "Net-(K1-Pad5)") (class "Default")
      (node (ref "K1") (pin "5") (pinfunction "5_5") (pintype "unspecified"))
      (node (ref "U21") (pin "2") (pinfunction "2_2") (pintype "unspecified"))
    )
    (net (code "30") (name "Net-(K2-Pad2)") (class "Default")
      (node (ref "K2") (pin "2") (pinfunction "2_2") (pintype "unspecified"))
      (node (ref "U20") (pin "1") (pinfunction "1_1") (pintype "unspecified"))
    )
    (net (code "31") (name "Net-(K2-Pad3)") (class "Default")
      (node (ref "K2") (pin "3") (pinfunction "3_3") (pintype "unspecified"))
      (node (ref "U20") (pin "3") (pinfunction "3_3") (pintype "unspecified"))
    )
    (net (code "32") (name "Net-(K2-Pad5)") (class "Default")
      (node (ref "K2") (pin "5") (pinfunction "5_5") (pintype "unspecified"))
      (node (ref "U20") (pin "2") (pinfunction "2_2") (pintype "unspecified"))
    )
    (net (code "33") (name "Net-(K3-Pad2)") (class "Default")
      (node (ref "K3") (pin "2") (pinfunction "2_2") (pintype "unspecified"))
      (node (ref "U12") (pin "1") (pinfunction "1_1") (pintype "unspecified"))
    )
    (net (code "34") (name "Net-(K3-Pad3)") (class "Default")
      (node (ref "K3") (pin "3") (pinfunction "3_3") (pintype "unspecified"))
      (node (ref "U12") (pin "3") (pinfunction "3_3") (pintype "unspecified"))
    )
    (net (code "35") (name "Net-(K3-Pad5)") (class "Default")
      (node (ref "K3") (pin "5") (pinfunction "5_5") (pintype "unspecified"))
      (node (ref "U12") (pin "2") (pinfunction "2_2") (pintype "unspecified"))
    )
    (net (code "36") (name "Net-(K4-Pad2)") (class "Default")
      (node (ref "K4") (pin "2") (pinfunction "2_2") (pintype "unspecified"))
      (node (ref "U19") (pin "1") (pinfunction "1_1") (pintype "unspecified"))
    )
    (net (code "37") (name "Net-(K4-Pad3)") (class "Default")
      (node (ref "K4") (pin "3") (pinfunction "3_3") (pintype "unspecified"))
      (node (ref "U19") (pin "3") (pinfunction "3_3") (pintype "unspecified"))
    )
    (net (code "38") (name "Net-(K4-Pad5)") (class "Default")
      (node (ref "K4") (pin "5") (pinfunction "5_5") (pintype "unspecified"))
      (node (ref "U19") (pin "2") (pinfunction "2_2") (pintype "unspecified"))
    )
    (net (code "39") (name "Net-(LED1-K)") (class "Default")
      (node (ref "LED1") (pin "1") (pinfunction "K_1") (pintype "unspecified"))
      (node (ref "R45") (pin "1") (pinfunction "1_1") (pintype "input"))
    )
    (net (code "40") (name "Net-(LED2-K)") (class "Default")
      (node (ref "LED2") (pin "1") (pinfunction "K_1") (pintype "unspecified"))
      (node (ref "R44") (pin "1") (pinfunction "1_1") (pintype "input"))
    )
    (net (code "41") (name "Net-(LED3-K)") (class "Default")
      (node (ref "LED3") (pin "1") (pinfunction "K_1") (pintype "unspecified"))
      (node (ref "R43") (pin "2") (pinfunction "2_2") (pintype "input"))
    )
    (net (code "42") (name "Net-(Q1-B)") (class "Default")
      (node (ref "Q1") (pin "1") (pinfunction "B_1") (pintype "unspecified"))
      (node (ref "R1") (pin "2") (pinfunction "2_2") (pintype "input"))
      (node (ref "R2") (pin "2") (pinfunction "2_2") (pintype "input"))
    )
    (net (code "43") (name "Net-(Q2-B)") (class "Default")
      (node (ref "Q2") (pin "1") (pinfunction "B_1") (pintype "unspecified"))
      (node (ref "R17") (pin "2") (pinfunction "2_2") (pintype "input"))
      (node (ref "R18") (pin "2") (pinfunction "2_2") (pintype "input"))
    )
    (net (code "44") (name "Net-(Q3-G)") (class "Default")
      (node (ref "Q3") (pin "1") (pinfunction "G_1") (pintype "unspecified"))
      (node (ref "R4") (pin "2") (pinfunction "2_2") (pintype "input"))
      (node (ref "R7") (pin "2") (pinfunction "2_2") (pintype "unspecified"))
    )
    (net (code "45") (name "Net-(Q4-B)") (class "Default")
      (node (ref "Q4") (pin "1") (pinfunction "B_1") (pintype "unspecified"))
      (node (ref "R19") (pin "2") (pinfunction "2_2") (pintype "input"))
      (node (ref "R20") (pin "2") (pinfunction "2_2") (pintype "input"))
    )
    (net (code "46") (name "Net-(Q5-B)") (class "Default")
      (node (ref "Q5") (pin "1") (pinfunction "B_1") (pintype "unspecified"))
      (node (ref "R21") (pin "2") (pinfunction "2_2") (pintype "input"))
      (node (ref "R22") (pin "2") (pinfunction "2_2") (pintype "input"))
    )
    (net (code "47") (name "Net-(Q6-G)") (class "Default")
      (node (ref "Q6") (pin "1") (pinfunction "G_1") (pintype "unspecified"))
      (node (ref "R23") (pin "2") (pinfunction "2_2") (pintype "unspecified"))
      (node (ref "R24") (pin "2") (pinfunction "2_2") (pintype "input"))
    )
    (net (code "48") (name "Net-(Q7-B)") (class "Default")
      (node (ref "Q7") (pin "1") (pinfunction "B_1") (pintype "unspecified"))
      (node (ref "R40") (pin "2") (pinfunction "2_2") (pintype "input"))
      (node (ref "R41") (pin "2") (pinfunction "2_2") (pintype "input"))
    )
    (net (code "49") (name "Net-(Q7-C)") (class "Default")
      (node (ref "BUZZER1") (pin "2") (pinfunction "2_2") (pintype "unspecified"))
      (node (ref "Q7") (pin "3") (pinfunction "C_3") (pintype "unspecified"))
    )
    (net (code "50") (name "Net-(Q8-D)") (class "Default")
      (node (ref "Q8") (pin "3") (pinfunction "D_3") (pintype "unspecified"))
      (node (ref "R36") (pin "1") (pinfunction "1_1") (pintype "unspecified"))
      (node (ref "U3") (pin "1") (pinfunction "1_1") (pintype "unspecified"))
      (node (ref "ZD1") (pin "2") (pinfunction "A_2") (pintype "unspecified"))
    )
    (net (code "51") (name "Net-(Q8-G)") (class "Default")
      (node (ref "Q8") (pin "1") (pinfunction "G_1") (pintype "unspecified"))
      (node (ref "R36") (pin "2") (pinfunction "2_2") (pintype "unspecified"))
      (node (ref "R39") (pin "1") (pinfunction "1_1") (pintype "input"))
      (node (ref "ZD1") (pin "1") (pinfunction "K_1") (pintype "unspecified"))
    )
    (net (code "52") (name "Net-(R5-Pad1)") (class "Default")
      (node (ref "R5") (pin "1") (pinfunction "1_1") (pintype "input"))
      (node (ref "U8") (pin "1") (pinfunction "1_1") (pintype "unspecified"))
    )
    (net (code "53") (name "Net-(R5-Pad2)") (class "Default")
      (node (ref "R5") (pin "2") (pinfunction "2_2") (pintype "input"))
      (node (ref "U7") (pin "1") (pinfunction "1_1") (pintype "unspecified"))
    )
    (net (code "54") (name "Net-(R12-Pad1)") (class "Default")
      (node (ref "R12") (pin "1") (pinfunction "1_1") (pintype "input"))
      (node (ref "U13") (pin "1") (pinfunction "1_1") (pintype "unspecified"))
    )
    (net (code "55") (name "Net-(R12-Pad2)") (class "Default")
      (node (ref "R12") (pin "2") (pinfunction "2_2") (pintype "input"))
      (node (ref "U14") (pin "1") (pinfunction "1_1") (pintype "unspecified"))
    )
    (net (code "56") (name "Net-(R13-Pad1)") (class "Default")
      (node (ref "R13") (pin "1") (pinfunction "1_1") (pintype "input"))
      (node (ref "U17") (pin "1") (pinfunction "1_1") (pintype "unspecified"))
    )
    (net (code "57") (name "Net-(R13-Pad2)") (class "Default")
      (node (ref "R13") (pin "2") (pinfunction "2_2") (pintype "input"))
      (node (ref "U15") (pin "1") (pinfunction "1_1") (pintype "unspecified"))
    )
    (net (code "58") (name "Net-(R16-Pad1)") (class "Default")
      (node (ref "R16") (pin "1") (pinfunction "1_1") (pintype "input"))
      (node (ref "U16") (pin "1") (pinfunction "1_1") (pintype "unspecified"))
    )
    (net (code "59") (name "Net-(R16-Pad2)") (class "Default")
      (node (ref "R16") (pin "2") (pinfunction "2_2") (pintype "input"))
      (node (ref "U18") (pin "1") (pinfunction "1_1") (pintype "unspecified"))
    )
    (net (code "60") (name "Net-(R31-Pad2)") (class "Default")
      (node (ref "R31") (pin "2") (pinfunction "2_2") (pintype "input"))
      (node (ref "U24") (pin "2") (pinfunction "2_2") (pintype "unspecified"))
    )
    (net (code "61") (name "Net-(R32-Pad2)") (class "Default")
      (node (ref "R32") (pin "2") (pinfunction "2_2") (pintype "input"))
      (node (ref "U26") (pin "2") (pinfunction "2_2") (pintype "unspecified"))
    )
    (net (code "62") (name "Net-(R33-Pad2)") (class "Default")
      (node (ref "R33") (pin "2") (pinfunction "2_2") (pintype "input"))
      (node (ref "U26") (pin "1") (pinfunction "1_1") (pintype "unspecified"))
    )
    (net (code "63") (name "Net-(R34-Pad2)") (class "Default")
      (node (ref "R34") (pin "2") (pinfunction "2_2") (pintype "input"))
      (node (ref "U10") (pin "2") (pinfunction "2_2") (pintype "unspecified"))
    )
    (net (code "64") (name "Net-(R35-Pad2)") (class "Default")
      (node (ref "R35") (pin "2") (pinfunction "2_2") (pintype "input"))
      (node (ref "U10") (pin "1") (pinfunction "1_1") (pintype "unspecified"))
    )
    (net (code "65") (name "Net-(R38-Pad2)") (class "Default")
      (node (ref "R38") (pin "2") (pinfunction "2_2") (pintype "input"))
      (node (ref "U24") (pin "1") (pinfunction "1_1") (pintype "unspecified"))
    )
    (net (code "66") (name "Net-(U7-Pad2)") (class "Default")
      (node (ref "U7") (pin "2") (pinfunction "2_2") (pintype "unspecified"))
      (node (ref "U8") (pin "2") (pinfunction "2_2") (pintype "unspecified"))
    )
    (net (code "67") (name "Net-(U13-Pad2)") (class "Default")
      (node (ref "U13") (pin "2") (pinfunction "2_2") (pintype "unspecified"))
      (node (ref "U14") (pin "2") (pinfunction "2_2") (pintype "unspecified"))
    )
    (net (code "68") (name "Net-(U15-Pad2)") (class "Default")
      (node (ref "U15") (pin "2") (pinfunction "2_2") (pintype "unspecified"))
      (node (ref "U17") (pin "2") (pinfunction "2_2") (pintype "unspecified"))
    )
    (net (code "69") (name "Net-(U16-Pad2)") (class "Default")
      (node (ref "U16") (pin "2") (pinfunction "2_2") (pintype "unspecified"))
      (node (ref "U18") (pin "2") (pinfunction "2_2") (pintype "unspecified"))
    )
    (net (code "70") (name "Net-(U23-A0)") (class "Default")
      (node (ref "J1") (pin "2") (pinfunction "2_2") (pintype "bidirectional"))
      (node (ref "J2") (pin "2") (pinfunction "2_2") (pintype "bidirectional"))
      (node (ref "J3") (pin "2") (pinfunction "2_2") (pintype "bidirectional"))
      (node (ref "J4") (pin "2") (pinfunction "2_2") (pintype "bidirectional"))
      (node (ref "U23") (pin "5") (pinfunction "A0_5") (pintype "unspecified"))
    )
    (net (code "71") (name "Net-(U23-CRITICAL)") (class "Default")
      (node (ref "R27") (pin "1") (pinfunction "1_1") (pintype "input"))
      (node (ref "U23") (pin "9") (pinfunction "CRITICAL_9") (pintype "unspecified"))
    )
    (net (code "72") (name "Net-(U23-IN+1)") (class "Default")
      (node (ref "C3") (pin "2") (pinfunction "2_2") (pintype "unspecified"))
      (node (ref "R31") (pin "1") (pinfunction "1_1") (pintype "input"))
      (node (ref "U23") (pin "12") (pinfunction "IN+1_12") (pintype "unspecified"))
    )
    (net (code "73") (name "Net-(U23-IN+2)") (class "Default")
      (node (ref "C5") (pin "2") (pinfunction "2_2") (pintype "unspecified"))
      (node (ref "R32") (pin "1") (pinfunction "1_1") (pintype "input"))
      (node (ref "U23") (pin "15") (pinfunction "IN+2_15") (pintype "unspecified"))
    )
    (net (code "74") (name "Net-(U23-IN+3)") (class "Default")
      (node (ref "C6") (pin "2") (pinfunction "2_2") (pintype "unspecified"))
      (node (ref "R34") (pin "1") (pinfunction "1_1") (pintype "input"))
      (node (ref "U23") (pin "2") (pinfunction "IN+3_2") (pintype "unspecified"))
    )
    (net (code "75") (name "Net-(U23-IN-1)") (class "Default")
      (node (ref "C3") (pin "1") (pinfunction "1_1") (pintype "unspecified"))
      (node (ref "R38") (pin "1") (pinfunction "1_1") (pintype "input"))
      (node (ref "U23") (pin "11") (pinfunction "IN-1_11") (pintype "unspecified"))
    )
    (net (code "76") (name "Net-(U23-IN-2)") (class "Default")
      (node (ref "C5") (pin "1") (pinfunction "1_1") (pintype "unspecified"))
      (node (ref "R33") (pin "1") (pinfunction "1_1") (pintype "input"))
      (node (ref "U23") (pin "14") (pinfunction "IN-2_14") (pintype "unspecified"))
    )
    (net (code "77") (name "Net-(U23-IN-3)") (class "Default")
      (node (ref "C6") (pin "1") (pinfunction "1_1") (pintype "unspecified"))
      (node (ref "R35") (pin "1") (pinfunction "1_1") (pintype "input"))
      (node (ref "U23") (pin "1") (pinfunction "IN-3_1") (pintype "unspecified"))
    )
    (net (code "78") (name "Net-(U23-PV)") (class "Default")
      (node (ref "R26") (pin "1") (pinfunction "1_1") (pintype "input"))
      (node (ref "U23") (pin "10") (pinfunction "PV_10") (pintype "unspecified"))
    )
    (net (code "79") (name "Net-(U23-TC)") (class "Default")
      (node (ref "R25") (pin "1") (pinfunction "1_1") (pintype "input"))
      (node (ref "U23") (pin "13") (pinfunction "TC_13") (pintype "unspecified"))
    )
    (net (code "80") (name "Net-(U23-WARNING)") (class "Default")
      (node (ref "R28") (pin "1") (pinfunction "1_1") (pintype "input"))
      (node (ref "U23") (pin "8") (pinfunction "WARNING_8") (pintype "unspecified"))
    )
    (net (code "81") (name "Net-(U28-CANH)") (class "Default")
      (node (ref "R8") (pin "2") (pinfunction "2_2") (pintype "input"))
      (node (ref "U2") (pin "2") (pinfunction "2_2") (pintype "unspecified"))
      (node (ref "U28") (pin "7") (pinfunction "CANH_7") (pintype "unspecified"))
    )
    (net (code "82") (name "Net-(U28-CANL)") (class "Default")
      (node (ref "J6") (pin "1") (pinfunction "1_1") (pintype "bidirectional"))
      (node (ref "U2") (pin "1") (pinfunction "1_1") (pintype "unspecified"))
      (node (ref "U28") (pin "6") (pinfunction "CANL_6") (pintype "unspecified"))
    )
    (net (code "83") (name "Net-(U28-RS)") (class "Default")
      (node (ref "R37") (pin "2") (pinfunction "2_2") (pintype "input"))
      (node (ref "U28") (pin "8") (pinfunction "RS_8") (pintype "unspecified"))
    )
    (net (code "84") (name "R") (class "Default")
      (node (ref "2") (pin "5") (pinfunction "IO4_5") (pintype "bidirectional"))
      (node (ref "U28") (pin "4") (pinfunction "R_4") (pintype "unspecified"))
    )
    (net (code "85") (name "VCC") (class "Default")
      (node (ref "BUZZER1") (pin "1") (pinfunction "+_1") (pintype "unspecified"))
      (node (ref "C2") (pin "1") (pinfunction "1_1") (pintype "input"))
      (node (ref "C8") (pin "2") (pinfunction "2_2") (pintype "input"))
      (node (ref "D1") (pin "1") (pinfunction "K_1") (pintype "unspecified"))
      (node (ref "D2") (pin "1") (pinfunction "K_1") (pintype "unspecified"))
      (node (ref "D3") (pin "1") (pinfunction "K_1") (pintype "unspecified"))
      (node (ref "D4") (pin "1") (pinfunction "K_1") (pintype "unspecified"))
      (node (ref "D5") (pin "1") (pinfunction "K_1") (pintype "unspecified"))
      (node (ref "D6") (pin "1") (pinfunction "K_1") (pintype "unspecified"))
      (node (ref "K1") (pin "4") (pinfunction "4_4") (pintype "unspecified"))
      (node (ref "K2") (pin "4") (pinfunction "4_4") (pintype "unspecified"))
      (node (ref "K3") (pin "4") (pinfunction "4_4") (pintype "unspecified"))
      (node (ref "K4") (pin "4") (pinfunction "4_4") (pintype "unspecified"))
      (node (ref "R39") (pin "2") (pinfunction "2_2") (pintype "input"))
      (node (ref "U1") (pin "3") (pinfunction "VIN_3") (pintype "unspecified"))
      (node (ref "U22") (pin "3") (pinfunction "VIN_3") (pintype "unspecified"))
      (node (ref "U3") (pin "2") (pinfunction "2_2") (pintype "unspecified"))
      (node (ref "U4") (pin "1") (pinfunction "1_1") (pintype "unspecified"))
      (node (ref "U5") (pin "1") (pinfunction "1_1") (pintype "unspecified"))
    )
    (net (code "86") (name "scl") (class "Default")
      (node (ref "2") (pin "14") (pinfunction "IO22_14") (pintype "bidirectional"))
      (node (ref "J3") (pin "1") (pinfunction "1_1") (pintype "bidirectional"))
      (node (ref "R30") (pin "1") (pinfunction "1_1") (pintype "input"))
      (node (ref "U23") (pin "6") (pinfunction "SCL_6") (pintype "unspecified"))
    )
    (net (code "87") (name "sda") (class "Default")
      (node (ref "2") (pin "11") (pinfunction "IO21_11") (pintype "bidirectional"))
      (node (ref "J4") (pin "1") (pinfunction "1_1") (pintype "bidirectional"))
      (node (ref "R29") (pin "1") (pinfunction "1_1") (pintype "input"))
      (node (ref "R9") (pin "1") (pinfunction "1_1") (pintype "input"))
      (node (ref "U11") (pin "3") (pinfunction "3_3") (pintype "unspecified"))
      (node (ref "U23") (pin "7") (pinfunction "SDA_7") (pintype "unspecified"))
      (node (ref "U29") (pin "3") (pinfunction "3_3") (pintype "unspecified"))
      (node (ref "U9") (pin "3") (pinfunction "3_3") (pintype "unspecified"))
    )
    (net (code "88") (name "unconnected-(2-EN-Pad16)") (class "Default")
      (node (ref "2") (pin "16") (pinfunction "EN_16") (pintype "bidirectional"))
    )
    (net (code "89") (name "unconnected-(2-IO1-Pad13)") (class "Default")
      (node (ref "2") (pin "13") (pinfunction "IO1_13") (pintype "bidirectional"))
    )
    (net (code "90") (name "unconnected-(2-IO3-Pad12)") (class "Default")
      (node (ref "2") (pin "12") (pinfunction "IO3_12") (pintype "bidirectional"))
    )
    (net (code "91") (name "unconnected-(2-IO12-Pad27)") (class "Default")
      (node (ref "2") (pin "27") (pinfunction "IO12_27") (pintype "bidirectional"))
    )
    (net (code "92") (name "unconnected-(2-IO14-Pad26)") (class "Default")
      (node (ref "2") (pin "26") (pinfunction "IO14_26") (pintype "bidirectional"))
    )
    (net (code "93") (name "unconnected-(2-IO15-Pad3)") (class "Default")
      (node (ref "2") (pin "3") (pinfunction "IO15_3") (pintype "bidirectional"))
    )
    (net (code "94") (name "unconnected-(2-IO32-Pad21)") (class "Default")
      (node (ref "2") (pin "21") (pinfunction "IO32_21") (pintype "bidirectional"))
    )
    (net (code "95") (name "unconnected-(2-IO33-Pad22)") (class "Default")
      (node (ref "2") (pin "22") (pinfunction "IO33_22") (pintype "bidirectional"))
    )
    (net (code "96") (name "unconnected-(2-VIN-Pad30)") (class "Default")
      (node (ref "2") (pin "30") (pinfunction "VIN_30") (pintype "bidirectional"))
    )
    (net (code "97") (name "unconnected-(U23-PAD-Pad17)") (class "Default")
      (node (ref "U23") (pin "17") (pinfunction "PAD_17") (pintype "unspecified"))
    )
    (net (code "98") (name "unconnected-(U28-GND-Pad2)") (class "Default")
      (node (ref "U28") (pin "2") (pinfunction "GND_2") (pintype "unspecified"))
    )
    (net (code "99") (name "unconnected-(U28-VREF-Pad5)") (class "Default")
      (node (ref "U28") (pin "5") (pinfunction "VREF_5") (pintype "unspecified"))
    )
  )
)
